# Micro.net
KiCad netlist of a schematic drawn in Altium Designer
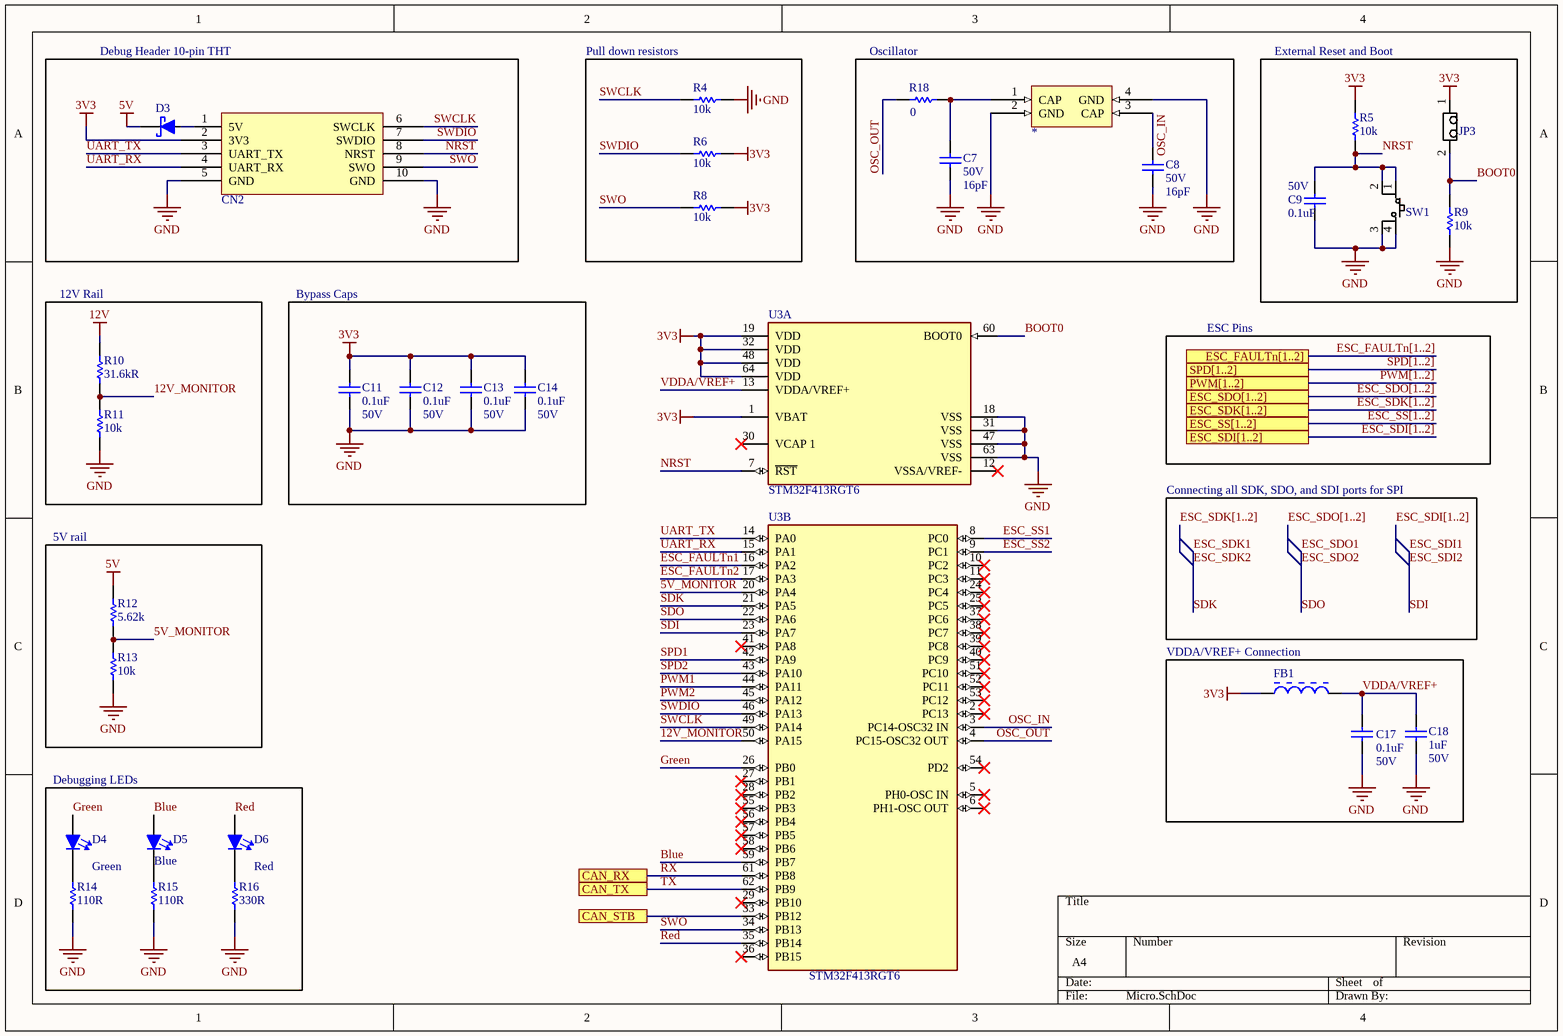
[diagram p0: Micro.SchDoc]

(export (version "E")
  (design (tool "Eeschema 10.0.6"))
  (components
    (comp (ref "*")
      (value "CRYSTAL 8.0MHZ 16PF SMD")
      (footprint "QFN250P750X520X140_HS-5M")
      (description "8MHz ±30ppm Crystal 16pF 80 Ohms 4-SMD, No Lead")
      (libsource (lib "AUVIC") (part "LFXTAL026380REEL"))
    )
    (comp (ref "C7")
      (value "16pF Ceramic 50V 5% 0603")
      (footprint "CAPC1608X90X35LL10T15")
      (description "Cap Ceramic 16pF 50V C0G 5% SMD 0603 125C Paper T/R")
      (fields
        (field (name "VOLTAGE") "50V")
        (field (name "TOLERANCE") "5%")
        (field (name "CAPACITANCE") "16pF")
      )
      (libsource (lib "AUVIC") (part "CAP"))
    )
    (comp (ref "C8")
      (value "16pF Ceramic 50V 5% 0603")
      (footprint "CAPC1608X90X35LL10T15")
      (description "Cap Ceramic 16pF 50V C0G 5% SMD 0603 125C Paper T/R")
      (fields
        (field (name "VOLTAGE") "50V")
        (field (name "TOLERANCE") "5%")
        (field (name "CAPACITANCE") "16pF")
      )
      (libsource (lib "AUVIC") (part "CAP"))
    )
    (comp (ref "C9")
      (value "CL10B104JB8NNNC")
      (footprint "FP-CL10-0_1-MFG")
      (description "CAP CER 0.1UF 50V X7R 0603")
      (fields
        (field (name "TOLERANCE") "5%")
        (field (name "VOLTAGE") "50V")
        (field (name "CAPACITANCE") "0.1uF")
      )
      (libsource (lib "AUVIC") (part "CAP-NP-2"))
    )
    (comp (ref "C11")
      (value "CL10B104JB8NNNC")
      (footprint "FP-CL10-0_1-IPC_A")
      (description "CAP CER 0.1UF 50V X7R 0603")
      (fields
        (field (name "TOLERANCE") "5%")
        (field (name "CAPACITANCE") "0.1uF")
        (field (name "VOLTAGE") "50V")
      )
      (libsource (lib "AUVIC") (part "CAP-NP-2"))
    )
    (comp (ref "C12")
      (value "CL10B104JB8NNNC")
      (footprint "FP-CL10-0_1-IPC_A")
      (description "CAP CER 0.1UF 50V X7R 0603")
      (fields
        (field (name "TOLERANCE") "5%")
        (field (name "CAPACITANCE") "0.1uF")
        (field (name "VOLTAGE") "50V")
      )
      (libsource (lib "AUVIC") (part "CAP-NP-2"))
    )
    (comp (ref "C13")
      (value "CL10B104JB8NNNC")
      (footprint "FP-CL10-0_1-IPC_A")
      (description "CAP CER 0.1UF 50V X7R 0603")
      (fields
        (field (name "TOLERANCE") "5%")
        (field (name "CAPACITANCE") "0.1uF")
        (field (name "VOLTAGE") "50V")
      )
      (libsource (lib "AUVIC") (part "CAP-NP-2"))
    )
    (comp (ref "C14")
      (value "CL10B104JB8NNNC")
      (footprint "FP-CL10-0_1-IPC_A")
      (description "CAP CER 0.1UF 50V X7R 0603")
      (fields
        (field (name "TOLERANCE") "5%")
        (field (name "CAPACITANCE") "0.1uF")
        (field (name "VOLTAGE") "50V")
      )
      (libsource (lib "AUVIC") (part "CAP-NP-2"))
    )
    (comp (ref "C17")
      (value "CL10B104JB8NNNC")
      (footprint "FP-CL10-0_1-MFG")
      (description "CAP CER 0.1UF 50V X7R 0603")
      (fields
        (field (name "TOLERANCE") "5%")
        (field (name "VOLTAGE") "50V")
        (field (name "CAPACITANCE") "0.1uF")
      )
      (libsource (lib "AUVIC") (part "CAP-NP-2"))
    )
    (comp (ref "C18")
      (value "CL21B105KBFNNNG")
      (footprint "0803 CAP")
      (description "SAMSUNG ELECTRO-MECHANICS - CL21B105KBFNNNG - MLCC CAPACITORS")
      (fields
        (field (name "CAPACITANCE") "1uF")
        (field (name "TOLERANCE") "10%")
        (field (name "VOLTAGE") "50V")
      )
      (libsource (lib "") (part "Symbol_4"))
    )
    (comp (ref "CN2")
      (value "ST Debug Header 10-pin THT")
      (footprint "10-pin shrouded header THT")
      (description "CONN HEADER VERT 10POS 2.54MM")
      (libsource (lib "AUVIC") (part "ST Debug Header 10-pin"))
    )
    (comp (ref "D3")
      (value "CUS08F30,H3F")
      (footprint "SC-76")
      (description "Diode Schottky 30V 800mA Surface Mount USC")
      (libsource (lib "") (part "Symbol_3"))
    )
    (comp (ref "D4")
      (value "LT Q39G-Q1OO-25-1")
      (footprint "FP-LB_Q39E-MFG")
      (description "LED GREEN DIFFUSED 0603 SMD")
      (fields (field (name "COLOR") "Green"))
      (libsource (lib "") (part "Symbol_1"))
    )
    (comp (ref "D5")
      (value "LBQ39E-N1OO-35-1")
      (footprint "FP-LB_Q39E-MFG")
      (description "LED BLUE DIFFUSED 0603 SMD")
      (fields (field (name "COLOR") "Blue"))
      (libsource (lib "") (part "Symbol_1"))
    )
    (comp (ref "D6")
      (value "LSQ976-NR-1")
      (footprint "FP-LB_Q39E-MFG")
      (description "LED Red 645nm 2-Pin Chip 0603(1608Metric) T/R")
      (fields (field (name "COLOR") "Red"))
      (libsource (lib "") (part "Symbol_1"))
    )
    (comp (ref "FB1")
      (value "BLM18AG601SN1D")
      (footprint "MURA-BLM18-F-H1-CHIP-2_V")
      (fields (field (name "TOLERANCE") "25%"))
      (libsource (lib "AUVIC") (part "MURA-FB-2"))
    )
    (comp (ref "JP3")
      (value "1x2 Male Header")
      (footprint "2X1 Males Header")
      (fields (field (name "MADE BY") "Andy Bates"))
      (libsource (lib "AUVIC") (part "1x2 Male Header"))
    )
    (comp (ref "R4")
      (value "10k")
      (footprint "RESC1608N(0603\")")
      (description "10kR, 1%, 1/10W, 0603 SMD")
      (fields (field (name "MADE BY") "Ashwin Sira"))
      (libsource (lib "AUVIC") (part "Symbol"))
    )
    (comp (ref "R5")
      (value "10k")
      (footprint "RESC1608N(0603\")")
      (description "10kR, 1%, 1/10W, 0603 SMD")
      (fields (field (name "MADE BY") "Ashwin Sira"))
      (libsource (lib "AUVIC") (part "Symbol"))
    )
    (comp (ref "R6")
      (value "10k")
      (footprint "RESC1608N(0603\")")
      (description "10kR, 1%, 1/10W, 0603 SMD")
      (fields (field (name "MADE BY") "Ashwin Sira"))
      (libsource (lib "AUVIC") (part "Symbol"))
    )
    (comp (ref "R8")
      (value "10k")
      (footprint "RESC1608N(0603\")")
      (description "10kR, 1%, 1/10W, 0603 SMD")
      (fields (field (name "MADE BY") "Ashwin Sira"))
      (libsource (lib "AUVIC") (part "Symbol"))
    )
    (comp (ref "R9")
      (value "10k")
      (footprint "RESC1608N(0603\")")
      (description "10kR, 1%, 1/10W, 0603 SMD")
      (fields (field (name "MADE BY") "Ashwin Sira"))
      (libsource (lib "AUVIC") (part "Symbol"))
    )
    (comp (ref "R10")
      (value "31.6kR")
      (footprint "RESC1608N(0603\")")
      (description "31.6kR, 1%, 1/10W, 0603, SMD")
      (fields (field (name "CREATED BY") "Robert Keen"))
      (libsource (lib "AUVIC") (part "Symbol"))
    )
    (comp (ref "R11")
      (value "10k")
      (footprint "RESC1608N(0603\")")
      (description "10kR, 1%, 1/10W, 0603 SMD")
      (fields (field (name "MADE BY") "Ashwin Sira"))
      (libsource (lib "AUVIC") (part "Symbol"))
    )
    (comp (ref "R12")
      (value "5.62k")
      (footprint "RESC1608N(0603\")")
      (description "5.62kR, 1%, 1/10W , 0603, SMD")
      (fields (field (name "PUBLISHER") "AUVic") (field (name "CREATED BY") "Andy Bates"))
      (libsource (lib "AUVIC") (part "Symbol"))
    )
    (comp (ref "R13")
      (value "10k")
      (footprint "RESC1608N(0603\")")
      (description "10kR, 1%, 1/10W, 0603 SMD")
      (fields (field (name "MADE BY") "Ashwin Sira"))
      (libsource (lib "AUVIC") (part "Symbol"))
    )
    (comp (ref "R14")
      (value "RC0603FR-07110RL")
      (footprint "RESC1608X55X25ML10T15")
      (description "RES SMD 110 OHM 1% 1/10W 0603")
      (fields (field (name "TOLERANCE") "1%") (field (name "RESISTANCE") "110R"))
      (libsource (lib "AUVIC") (part "RES"))
    )
    (comp (ref "R15")
      (value "RC0603FR-07110RL")
      (footprint "RESC1608X55X25ML10T15")
      (description "RES SMD 110 OHM 1% 1/10W 0603")
      (fields (field (name "TOLERANCE") "1%") (field (name "RESISTANCE") "110R"))
      (libsource (lib "AUVIC") (part "RES"))
    )
    (comp (ref "R16")
      (value "CRCW0603330RFKEA")
      (footprint "FP-CRCW0603-e3-IPC_C")
      (description "Res Thick Film 0603 330 Ohm 1% 0.1W(1/10W) +/-100ppm/ßC Pad SMD Automotive T/R")
      (fields (field (name "TOLERANCE") "1%") (field (name "RESISTANCE") "330R"))
      (libsource (lib "AUVIC") (part "RES"))
    )
    (comp (ref "R18")
      (value "0")
      (footprint "RESC1608N(0603\")")
      (description "10kR, 1%, 1/10W, 0603 SMD")
      (fields (field (name "MADE BY") "Ashwin Sira"))
      (libsource (lib "AUVIC") (part "Symbol"))
    )
    (comp (ref "SW1")
      (value "PTS645SL43SMTR92LFS")
      (footprint "4-SPST-NO")
      (description "Black Switch Tactile N.O. SPST Round Button Gull Wing 0.05A 12VDC 100000Cycles 1.27N SMD T/R")
      (libsource (lib "") (part "Symbol_2"))
    )
    (comp (ref "U3")
      (value "STM32F413RGT6")
      (footprint "FP-LQFP64-5W-IPC_A")
      (description "STMICROELECTRONICS - STM32F413RGT6 - MCU, ARM CORTEX-M4, 100MHZ, LQFP-64")
      (libsource (lib "AUVIC") (part "7f3deadac312a1e532344b4e443717e"))
    )
  )
  (nets
    (net (code "1") (name "/5V_MONITOR") (class "Default")
      (node (ref "R12") (pin "1") (pinfunction "1_1") (pintype "passive"))
      (node (ref "R13") (pin "2") (pinfunction "2_2") (pintype "passive"))
      (node (ref "U3") (pin "20") (pinfunction "PA4_20") (pintype "bidirectional"))
    )
    (net (code "2") (name "/12V_MONITOR") (class "Default")
      (node (ref "R10") (pin "1") (pinfunction "1_1") (pintype "passive"))
      (node (ref "R11") (pin "2") (pinfunction "2_2") (pintype "passive"))
      (node (ref "U3") (pin "50") (pinfunction "PA15_50") (pintype "bidirectional"))
    )
    (net (code "3") (name "/BOOT0") (class "Default")
      (node (ref "JP3") (pin "2") (pinfunction "2_2") (pintype "passive"))
      (node (ref "R9") (pin "2") (pinfunction "2_2") (pintype "passive"))
      (node (ref "U3") (pin "60") (pinfunction "BOOT0_60") (pintype "input"))
    )
    (net (code "4") (name "/Blue") (class "Default")
      (node (ref "D5") (pin "2") (pinfunction "Anode_2") (pintype "passive"))
      (node (ref "U3") (pin "59") (pinfunction "PB7_59") (pintype "bidirectional"))
    )
    (net (code "5") (name "/CAN_STB") (class "Default")
      (node (ref "U3") (pin "33") (pinfunction "PB12_33") (pintype "bidirectional"))
    )
    (net (code "6") (name "/ESC_FAULTn1") (class "Default")
      (node (ref "U3") (pin "16") (pinfunction "PA2_16") (pintype "bidirectional"))
    )
    (net (code "7") (name "/ESC_FAULTn2") (class "Default")
      (node (ref "U3") (pin "17") (pinfunction "PA3_17") (pintype "bidirectional"))
    )
    (net (code "9") (name "/ESC_SDI2") (class "Default")
      (node (ref "U3") (pin "23") (pinfunction "PA7_23") (pintype "bidirectional"))
    )
    (net (code "11") (name "/ESC_SDK2") (class "Default")
      (node (ref "U3") (pin "21") (pinfunction "PA5_21") (pintype "bidirectional"))
    )
    (net (code "13") (name "/ESC_SDO2") (class "Default")
      (node (ref "U3") (pin "22") (pinfunction "PA6_22") (pintype "bidirectional"))
    )
    (net (code "15") (name "/ESC_SS1") (class "Default")
      (node (ref "U3") (pin "8") (pinfunction "PC0_8") (pintype "bidirectional"))
    )
    (net (code "16") (name "/ESC_SS2") (class "Default")
      (node (ref "U3") (pin "9") (pinfunction "PC1_9") (pintype "bidirectional"))
    )
    (net (code "18") (name "/Green") (class "Default")
      (node (ref "D4") (pin "2") (pinfunction "Anode_2") (pintype "passive"))
      (node (ref "U3") (pin "26") (pinfunction "PB0_26") (pintype "bidirectional"))
    )
    (net (code "19") (name "/NRST") (class "Default")
      (node (ref "C9") (pin "2") (pinfunction "2_2") (pintype "passive"))
      (node (ref "CN2") (pin "8") (pinfunction "NRST_8") (pintype "passive"))
      (node (ref "R5") (pin "1") (pinfunction "1_1") (pintype "passive"))
      (node (ref "SW1") (pin "1") (pinfunction "1_1") (pintype "passive"))
      (node (ref "SW1") (pin "2") (pinfunction "2_2") (pintype "passive"))
      (node (ref "U3") (pin "7") (pinfunction "~{RST}_7") (pintype "bidirectional"))
    )
    (net (code "20") (name "/OSC_IN") (class "Default")
      (node (ref "*") (pin "3") (pinfunction "CAP_3") (pintype "input"))
      (node (ref "C8") (pin "2") (pinfunction "2_2") (pintype "passive"))
      (node (ref "U3") (pin "3") (pinfunction "PC14-OSC32_IN_3") (pintype "bidirectional"))
    )
    (net (code "21") (name "/OSC_OUT") (class "Default")
      (node (ref "R18") (pin "1") (pinfunction "1_1") (pintype "passive"))
      (node (ref "U3") (pin "4") (pinfunction "PC15-OSC32_OUT_4") (pintype "bidirectional"))
    )
    (net (code "22") (name "/PWM1") (class "Default")
      (node (ref "U3") (pin "44") (pinfunction "PA11_44") (pintype "bidirectional"))
    )
    (net (code "23") (name "/PWM2") (class "Default")
      (node (ref "U3") (pin "45") (pinfunction "PA12_45") (pintype "bidirectional"))
    )
    (net (code "25") (name "/RX") (class "Default")
      (node (ref "U3") (pin "61") (pinfunction "PB8_61") (pintype "bidirectional"))
    )
    (net (code "26") (name "/Red") (class "Default")
      (node (ref "D6") (pin "2") (pinfunction "Anode_2") (pintype "passive"))
      (node (ref "U3") (pin "35") (pinfunction "PB14_35") (pintype "bidirectional"))
    )
    (net (code "27") (name "/SPD1") (class "Default")
      (node (ref "U3") (pin "42") (pinfunction "PA9_42") (pintype "bidirectional"))
    )
    (net (code "28") (name "/SPD2") (class "Default")
      (node (ref "U3") (pin "43") (pinfunction "PA10_43") (pintype "bidirectional"))
    )
    (net (code "30") (name "/SWCLK") (class "Default")
      (node (ref "CN2") (pin "6") (pinfunction "SWCLK_6") (pintype "passive"))
      (node (ref "R4") (pin "1") (pinfunction "1_1") (pintype "passive"))
      (node (ref "U3") (pin "49") (pinfunction "PA14_49") (pintype "bidirectional"))
    )
    (net (code "31") (name "/SWDIO") (class "Default")
      (node (ref "CN2") (pin "7") (pinfunction "SWDIO_7") (pintype "passive"))
      (node (ref "R6") (pin "1") (pinfunction "1_1") (pintype "passive"))
      (node (ref "U3") (pin "46") (pinfunction "PA13_46") (pintype "bidirectional"))
    )
    (net (code "32") (name "/SWO") (class "Default")
      (node (ref "CN2") (pin "9") (pinfunction "SWO_9") (pintype "passive"))
      (node (ref "R8") (pin "1") (pinfunction "1_1") (pintype "passive"))
      (node (ref "U3") (pin "34") (pinfunction "PB13_34") (pintype "bidirectional"))
    )
    (net (code "33") (name "/TX") (class "Default")
      (node (ref "U3") (pin "62") (pinfunction "PB9_62") (pintype "bidirectional"))
    )
    (net (code "34") (name "/UART_RX") (class "Default")
      (node (ref "CN2") (pin "4") (pinfunction "UART_RX_4") (pintype "passive"))
      (node (ref "U3") (pin "15") (pinfunction "PA1_15") (pintype "bidirectional"))
    )
    (net (code "35") (name "/UART_TX") (class "Default")
      (node (ref "CN2") (pin "3") (pinfunction "UART_TX_3") (pintype "passive"))
      (node (ref "U3") (pin "14") (pinfunction "PA0_14") (pintype "bidirectional"))
    )
    (net (code "36") (name "/VDDA{slash}VREF+") (class "Default")
      (node (ref "C17") (pin "1") (pinfunction "1_1") (pintype "passive"))
      (node (ref "C18") (pin "2") (pinfunction "2_2") (pintype "passive"))
      (node (ref "FB1") (pin "2") (pinfunction "2_2") (pintype "passive"))
      (node (ref "U3") (pin "13") (pinfunction "VDDA/VREF+_13") (pintype "power_in"))
    )
    (net (code "37") (name "3V3") (class "Default")
      (node (ref "C11") (pin "2") (pinfunction "2_2") (pintype "passive"))
      (node (ref "C12") (pin "2") (pinfunction "2_2") (pintype "passive"))
      (node (ref "C13") (pin "2") (pinfunction "2_2") (pintype "passive"))
      (node (ref "C14") (pin "2") (pinfunction "2_2") (pintype "passive"))
      (node (ref "CN2") (pin "2") (pinfunction "3V3_2") (pintype "passive"))
      (node (ref "FB1") (pin "1") (pinfunction "1_1") (pintype "passive"))
      (node (ref "JP3") (pin "1") (pinfunction "1_1") (pintype "passive"))
      (node (ref "R5") (pin "2") (pinfunction "2_2") (pintype "passive"))
      (node (ref "R6") (pin "2") (pinfunction "2_2") (pintype "passive"))
      (node (ref "R8") (pin "2") (pinfunction "2_2") (pintype "passive"))
      (node (ref "U3") (pin "1") (pinfunction "VBAT_1") (pintype "power_in"))
      (node (ref "U3") (pin "19") (pinfunction "VDD_19") (pintype "power_in"))
      (node (ref "U3") (pin "32") (pinfunction "VDD_32") (pintype "power_in"))
      (node (ref "U3") (pin "48") (pinfunction "VDD_48") (pintype "power_in"))
      (node (ref "U3") (pin "64") (pinfunction "VDD_64") (pintype "power_in"))
    )
    (net (code "38") (name "5V") (class "Default")
      (node (ref "D3") (pin "K") (pinfunction "Cathode_K") (pintype "passive"))
      (node (ref "R12") (pin "2") (pinfunction "2_2") (pintype "passive"))
    )
    (net (code "39") (name "12V") (class "Default")
      (node (ref "R10") (pin "2") (pinfunction "2_2") (pintype "passive"))
    )
    (net (code "40") (name "GND") (class "Default")
      (node (ref "*") (pin "2") (pinfunction "GND_2") (pintype "input"))
      (node (ref "*") (pin "4") (pinfunction "GND_4") (pintype "input"))
      (node (ref "C11") (pin "1") (pinfunction "1_1") (pintype "passive"))
      (node (ref "C12") (pin "1") (pinfunction "1_1") (pintype "passive"))
      (node (ref "C13") (pin "1") (pinfunction "1_1") (pintype "passive"))
      (node (ref "C14") (pin "1") (pinfunction "1_1") (pintype "passive"))
      (node (ref "C17") (pin "2") (pinfunction "2_2") (pintype "passive"))
      (node (ref "C18") (pin "1") (pinfunction "1_1") (pintype "passive"))
      (node (ref "C7") (pin "1") (pinfunction "1_1") (pintype "passive"))
      (node (ref "C8") (pin "1") (pinfunction "1_1") (pintype "passive"))
      (node (ref "C9") (pin "1") (pinfunction "1_1") (pintype "passive"))
      (node (ref "CN2") (pin "10") (pinfunction "GND_10") (pintype "passive"))
      (node (ref "CN2") (pin "5") (pinfunction "GND_5") (pintype "passive"))
      (node (ref "R11") (pin "1") (pinfunction "1_1") (pintype "passive"))
      (node (ref "R13") (pin "1") (pinfunction "1_1") (pintype "passive"))
      (node (ref "R14") (pin "1") (pinfunction "1_1") (pintype "passive"))
      (node (ref "R15") (pin "1") (pinfunction "1_1") (pintype "passive"))
      (node (ref "R16") (pin "1") (pinfunction "1_1") (pintype "passive"))
      (node (ref "R4") (pin "2") (pinfunction "2_2") (pintype "passive"))
      (node (ref "R9") (pin "1") (pinfunction "1_1") (pintype "passive"))
      (node (ref "SW1") (pin "3") (pinfunction "3_3") (pintype "passive"))
      (node (ref "SW1") (pin "4") (pinfunction "4_4") (pintype "passive"))
      (node (ref "U3") (pin "18") (pinfunction "VSS_18") (pintype "power_in"))
      (node (ref "U3") (pin "31") (pinfunction "VSS_31") (pintype "power_in"))
      (node (ref "U3") (pin "47") (pinfunction "VSS_47") (pintype "power_in"))
      (node (ref "U3") (pin "63") (pinfunction "VSS_63") (pintype "power_in"))
    )
    (net (code "41") (name "Net-(*-CAP-Pad1)") (class "Default")
      (node (ref "*") (pin "1") (pinfunction "CAP_1") (pintype "input"))
      (node (ref "C7") (pin "2") (pinfunction "2_2") (pintype "passive"))
      (node (ref "R18") (pin "2") (pinfunction "2_2") (pintype "passive"))
    )
    (net (code "42") (name "Net-(CN2-5V)") (class "Default")
      (node (ref "CN2") (pin "1") (pinfunction "5V_1") (pintype "passive"))
      (node (ref "D3") (pin "A") (pinfunction "Anode_A") (pintype "passive"))
    )
    (net (code "43") (name "Net-(D4-Cathode)") (class "Default")
      (node (ref "D4") (pin "1") (pinfunction "Cathode_1") (pintype "passive"))
      (node (ref "R14") (pin "2") (pinfunction "2_2") (pintype "passive"))
    )
    (net (code "44") (name "Net-(D5-Cathode)") (class "Default")
      (node (ref "D5") (pin "1") (pinfunction "Cathode_1") (pintype "passive"))
      (node (ref "R15") (pin "2") (pinfunction "2_2") (pintype "passive"))
    )
    (net (code "45") (name "Net-(D6-Cathode)") (class "Default")
      (node (ref "D6") (pin "1") (pinfunction "Cathode_1") (pintype "passive"))
      (node (ref "R16") (pin "2") (pinfunction "2_2") (pintype "passive"))
    )
    (net (code "46") (name "unconnected-(U3A-VCAP_1-Pad30)") (class "Default")
      (node (ref "U3") (pin "30") (pinfunction "VCAP_1_30") (pintype "power_in+no_connect"))
    )
    (net (code "47") (name "unconnected-(U3A-VSSA{slash}VREF--Pad12)") (class "Default")
      (node (ref "U3") (pin "12") (pinfunction "VSSA/VREF-_12") (pintype "power_in+no_connect"))
    )
    (net (code "48") (name "unconnected-(U3B-PA8-Pad41)") (class "Default")
      (node (ref "U3") (pin "41") (pinfunction "PA8_41") (pintype "bidirectional+no_connect"))
    )
    (net (code "49") (name "unconnected-(U3B-PB1-Pad27)") (class "Default")
      (node (ref "U3") (pin "27") (pinfunction "PB1_27") (pintype "bidirectional+no_connect"))
    )
    (net (code "50") (name "unconnected-(U3B-PB2-Pad28)") (class "Default")
      (node (ref "U3") (pin "28") (pinfunction "PB2_28") (pintype "bidirectional+no_connect"))
    )
    (net (code "51") (name "unconnected-(U3B-PB3-Pad55)") (class "Default")
      (node (ref "U3") (pin "55") (pinfunction "PB3_55") (pintype "bidirectional+no_connect"))
    )
    (net (code "52") (name "unconnected-(U3B-PB4-Pad56)") (class "Default")
      (node (ref "U3") (pin "56") (pinfunction "PB4_56") (pintype "bidirectional+no_connect"))
    )
    (net (code "53") (name "unconnected-(U3B-PB5-Pad57)") (class "Default")
      (node (ref "U3") (pin "57") (pinfunction "PB5_57") (pintype "bidirectional+no_connect"))
    )
    (net (code "54") (name "unconnected-(U3B-PB6-Pad58)") (class "Default")
      (node (ref "U3") (pin "58") (pinfunction "PB6_58") (pintype "bidirectional+no_connect"))
    )
    (net (code "55") (name "unconnected-(U3B-PB10-Pad29)") (class "Default")
      (node (ref "U3") (pin "29") (pinfunction "PB10_29") (pintype "bidirectional+no_connect"))
    )
    (net (code "56") (name "unconnected-(U3B-PB15-Pad36)") (class "Default")
      (node (ref "U3") (pin "36") (pinfunction "PB15_36") (pintype "bidirectional+no_connect"))
    )
    (net (code "57") (name "unconnected-(U3B-PC2-Pad10)") (class "Default")
      (node (ref "U3") (pin "10") (pinfunction "PC2_10") (pintype "bidirectional+no_connect"))
    )
    (net (code "58") (name "unconnected-(U3B-PC3-Pad11)") (class "Default")
      (node (ref "U3") (pin "11") (pinfunction "PC3_11") (pintype "bidirectional+no_connect"))
    )
    (net (code "59") (name "unconnected-(U3B-PC4-Pad24)") (class "Default")
      (node (ref "U3") (pin "24") (pinfunction "PC4_24") (pintype "bidirectional+no_connect"))
    )
    (net (code "60") (name "unconnected-(U3B-PC5-Pad25)") (class "Default")
      (node (ref "U3") (pin "25") (pinfunction "PC5_25") (pintype "bidirectional+no_connect"))
    )
    (net (code "61") (name "unconnected-(U3B-PC6-Pad37)") (class "Default")
      (node (ref "U3") (pin "37") (pinfunction "PC6_37") (pintype "bidirectional+no_connect"))
    )
    (net (code "62") (name "unconnected-(U3B-PC7-Pad38)") (class "Default")
      (node (ref "U3") (pin "38") (pinfunction "PC7_38") (pintype "bidirectional+no_connect"))
    )
    (net (code "63") (name "unconnected-(U3B-PC8-Pad39)") (class "Default")
      (node (ref "U3") (pin "39") (pinfunction "PC8_39") (pintype "bidirectional+no_connect"))
    )
    (net (code "64") (name "unconnected-(U3B-PC9-Pad40)") (class "Default")
      (node (ref "U3") (pin "40") (pinfunction "PC9_40") (pintype "bidirectional+no_connect"))
    )
    (net (code "65") (name "unconnected-(U3B-PC10-Pad51)") (class "Default")
      (node (ref "U3") (pin "51") (pinfunction "PC10_51") (pintype "bidirectional+no_connect"))
    )
    (net (code "66") (name "unconnected-(U3B-PC11-Pad52)") (class "Default")
      (node (ref "U3") (pin "52") (pinfunction "PC11_52") (pintype "bidirectional+no_connect"))
    )
    (net (code "67") (name "unconnected-(U3B-PC12-Pad53)") (class "Default")
      (node (ref "U3") (pin "53") (pinfunction "PC12_53") (pintype "bidirectional+no_connect"))
    )
    (net (code "68") (name "unconnected-(U3B-PC13-Pad2)") (class "Default")
      (node (ref "U3") (pin "2") (pinfunction "PC13_2") (pintype "bidirectional+no_connect"))
    )
    (net (code "69") (name "unconnected-(U3B-PD2-Pad54)") (class "Default")
      (node (ref "U3") (pin "54") (pinfunction "PD2_54") (pintype "bidirectional+no_connect"))
    )
    (net (code "70") (name "unconnected-(U3B-PH0-OSC_IN-Pad5)") (class "Default")
      (node (ref "U3") (pin "5") (pinfunction "PH0-OSC_IN_5") (pintype "bidirectional+no_connect"))
    )
    (net (code "71") (name "unconnected-(U3B-PH1-OSC_OUT-Pad6)") (class "Default")
      (node (ref "U3") (pin "6") (pinfunction "PH1-OSC_OUT_6") (pintype "bidirectional+no_connect"))
    )
  )
)
